# DSPCONN_0-3.net
KiCad netlist of a schematic drawn in Altium Designer
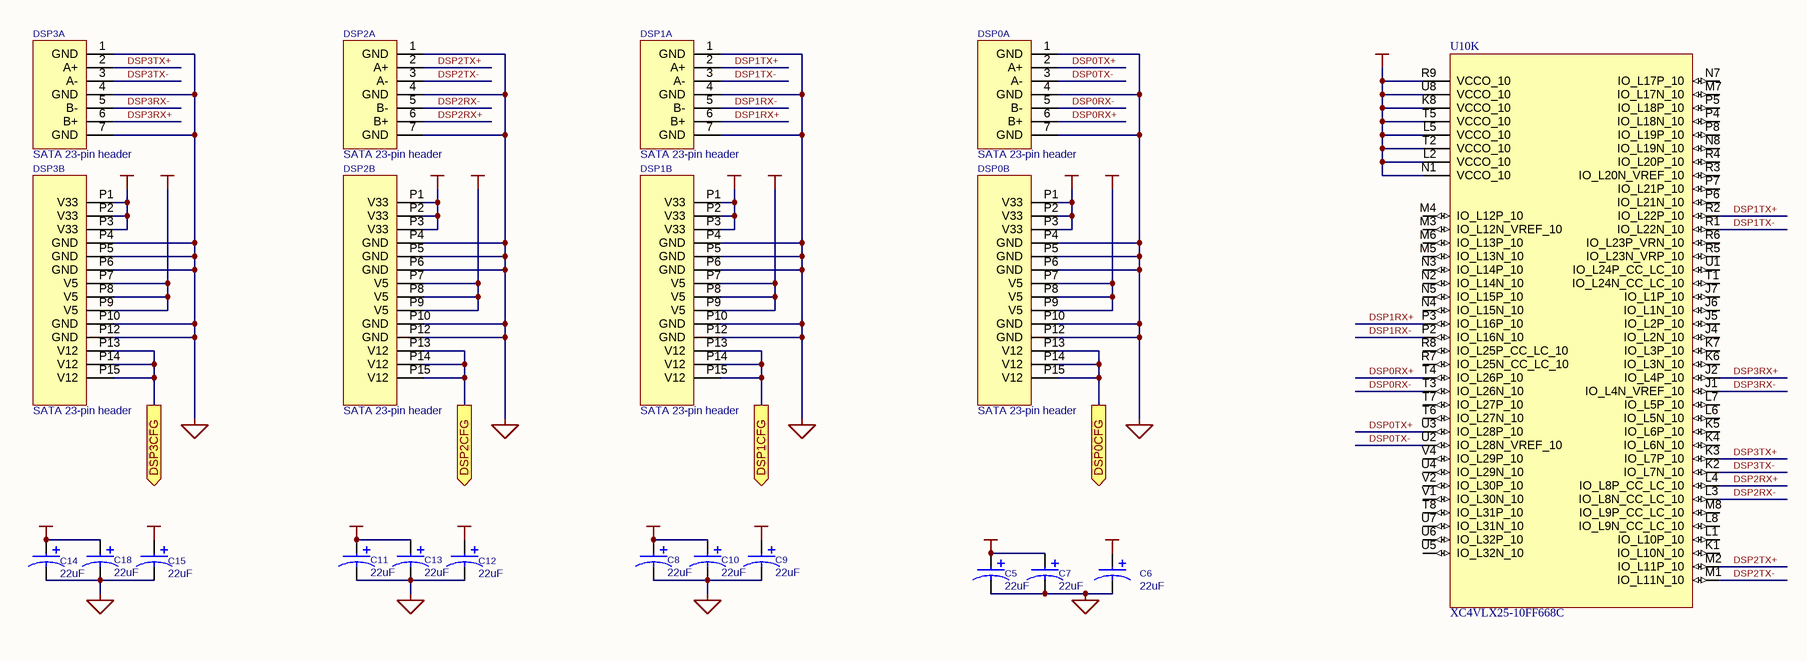
[diagram p0: DSPCONN.0-3.SCHDOC]

(export (version "E")
  (design (tool "Eeschema 10.0.6"))
  (components
    (comp (ref "C5")
      (value "22uF")
      (footprint "6032")
      (description "Standard Capacitor")
      (libsource (lib "parts") (part "POLCAP2"))
    )
    (comp (ref "C6")
      (value "22uF")
      (footprint "6032")
      (description "Standard Capacitor")
      (libsource (lib "parts") (part "POLCAP2"))
    )
    (comp (ref "C7")
      (value "22uF")
      (footprint "6032")
      (description "Standard Capacitor")
      (libsource (lib "parts") (part "POLCAP2"))
    )
    (comp (ref "C8")
      (value "22uF")
      (footprint "6032")
      (description "Standard Capacitor")
      (libsource (lib "parts") (part "POLCAP2"))
    )
    (comp (ref "C9")
      (value "22uF")
      (footprint "6032")
      (description "Standard Capacitor")
      (libsource (lib "parts") (part "POLCAP2"))
    )
    (comp (ref "C10")
      (value "22uF")
      (footprint "6032")
      (description "Standard Capacitor")
      (libsource (lib "parts") (part "POLCAP2"))
    )
    (comp (ref "C11")
      (value "22uF")
      (footprint "6032")
      (description "Standard Capacitor")
      (libsource (lib "parts") (part "POLCAP2"))
    )
    (comp (ref "C12")
      (value "22uF")
      (footprint "6032")
      (description "Standard Capacitor")
      (libsource (lib "parts") (part "POLCAP2"))
    )
    (comp (ref "C13")
      (value "22uF")
      (footprint "6032")
      (description "Standard Capacitor")
      (libsource (lib "parts") (part "POLCAP2"))
    )
    (comp (ref "C14")
      (value "22uF")
      (footprint "6032")
      (description "Standard Capacitor")
      (libsource (lib "parts") (part "POLCAP2"))
    )
    (comp (ref "C15")
      (value "22uF")
      (footprint "6032")
      (description "Standard Capacitor")
      (libsource (lib "parts") (part "POLCAP2"))
    )
    (comp (ref "C18")
      (value "22uF")
      (footprint "6032")
      (description "Standard Capacitor")
      (libsource (lib "parts") (part "POLCAP2"))
    )
    (comp (ref "DSP0")
      (value "SATA 23-pin header")
      (footprint "MOLEX 87713-1001")
      (libsource (lib "parts") (part "SATA-23"))
    )
    (comp (ref "DSP1")
      (value "SATA 23-pin header")
      (footprint "MOLEX 87713-1001")
      (libsource (lib "parts") (part "SATA-23"))
    )
    (comp (ref "DSP2")
      (value "SATA 23-pin header")
      (footprint "MOLEX 87713-1001")
      (libsource (lib "parts") (part "SATA-23"))
    )
    (comp (ref "DSP3")
      (value "SATA 23-pin header")
      (footprint "MOLEX 87713-1001")
      (libsource (lib "parts") (part "SATA-23"))
    )
    (comp (ref "U10")
      (value "XC4VLX25-10FF668C")
      (footprint "Xilinx FF668")
      (description "Xilinx Virtex-4")
      (libsource (lib "parts") (part "XC4VLX25-10FF668C"))
    )
  )
  (nets
    (net (code "1") (name "+2.5VCC") (class "Default")
      (node (ref "U10") (pin "K8") (pinfunction "VCCO_10_K8") (pintype "power_in"))
      (node (ref "U10") (pin "L2") (pinfunction "VCCO_10_L2") (pintype "power_in"))
      (node (ref "U10") (pin "L5") (pinfunction "VCCO_10_L5") (pintype "power_in"))
      (node (ref "U10") (pin "N1") (pinfunction "VCCO_10_N1") (pintype "power_in"))
      (node (ref "U10") (pin "R9") (pinfunction "VCCO_10_R9") (pintype "power_in"))
      (node (ref "U10") (pin "T2") (pinfunction "VCCO_10_T2") (pintype "power_in"))
      (node (ref "U10") (pin "T5") (pinfunction "VCCO_10_T5") (pintype "power_in"))
      (node (ref "U10") (pin "U8") (pinfunction "VCCO_10_U8") (pintype "power_in"))
    )
    (net (code "2") (name "+5VCC") (class "Default")
      (node (ref "C12") (pin "1") (pintype "passive"))
      (node (ref "C15") (pin "1") (pintype "passive"))
      (node (ref "C6") (pin "1") (pintype "passive"))
      (node (ref "C9") (pin "1") (pintype "passive"))
      (node (ref "DSP0") (pin "P7") (pinfunction "V5_P7") (pintype "passive"))
      (node (ref "DSP0") (pin "P8") (pinfunction "V5_P8") (pintype "passive"))
      (node (ref "DSP0") (pin "P9") (pinfunction "V5_P9") (pintype "passive"))
      (node (ref "DSP1") (pin "P7") (pinfunction "V5_P7") (pintype "passive"))
      (node (ref "DSP1") (pin "P8") (pinfunction "V5_P8") (pintype "passive"))
      (node (ref "DSP1") (pin "P9") (pinfunction "V5_P9") (pintype "passive"))
      (node (ref "DSP2") (pin "P7") (pinfunction "V5_P7") (pintype "passive"))
      (node (ref "DSP2") (pin "P8") (pinfunction "V5_P8") (pintype "passive"))
      (node (ref "DSP2") (pin "P9") (pinfunction "V5_P9") (pintype "passive"))
      (node (ref "DSP3") (pin "P7") (pinfunction "V5_P7") (pintype "passive"))
      (node (ref "DSP3") (pin "P8") (pinfunction "V5_P8") (pintype "passive"))
      (node (ref "DSP3") (pin "P9") (pinfunction "V5_P9") (pintype "passive"))
    )
    (net (code "3") (name "/DSP0CFG") (class "Default")
      (node (ref "DSP0") (pin "P13") (pinfunction "V12_P13") (pintype "passive"))
      (node (ref "DSP0") (pin "P14") (pinfunction "V12_P14") (pintype "passive"))
      (node (ref "DSP0") (pin "P15") (pinfunction "V12_P15") (pintype "passive"))
    )
    (net (code "4") (name "/DSP0RX+") (class "Default")
      (node (ref "DSP0") (pin "6") (pinfunction "B+_6") (pintype "passive"))
      (node (ref "U10") (pin "T4") (pinfunction "IO_L26P_10_T4") (pintype "bidirectional"))
    )
    (net (code "5") (name "/DSP0RX-") (class "Default")
      (node (ref "DSP0") (pin "5") (pinfunction "B-_5") (pintype "passive"))
      (node (ref "U10") (pin "T3") (pinfunction "IO_L26N_10_T3") (pintype "bidirectional"))
    )
    (net (code "6") (name "/DSP0TX+") (class "Default")
      (node (ref "DSP0") (pin "2") (pinfunction "A+_2") (pintype "passive"))
      (node (ref "U10") (pin "U3") (pinfunction "IO_L28P_10_U3") (pintype "bidirectional"))
    )
    (net (code "7") (name "/DSP0TX-") (class "Default")
      (node (ref "DSP0") (pin "3") (pinfunction "A-_3") (pintype "passive"))
      (node (ref "U10") (pin "U2") (pinfunction "IO_L28N_VREF_10_U2") (pintype "bidirectional"))
    )
    (net (code "8") (name "/DSP1CFG") (class "Default")
      (node (ref "DSP1") (pin "P13") (pinfunction "V12_P13") (pintype "passive"))
      (node (ref "DSP1") (pin "P14") (pinfunction "V12_P14") (pintype "passive"))
      (node (ref "DSP1") (pin "P15") (pinfunction "V12_P15") (pintype "passive"))
    )
    (net (code "9") (name "/DSP1RX+") (class "Default")
      (node (ref "DSP1") (pin "6") (pinfunction "B+_6") (pintype "passive"))
      (node (ref "U10") (pin "P3") (pinfunction "IO_L16P_10_P3") (pintype "bidirectional"))
    )
    (net (code "10") (name "/DSP1RX-") (class "Default")
      (node (ref "DSP1") (pin "5") (pinfunction "B-_5") (pintype "passive"))
      (node (ref "U10") (pin "P2") (pinfunction "IO_L16N_10_P2") (pintype "bidirectional"))
    )
    (net (code "11") (name "/DSP1TX+") (class "Default")
      (node (ref "DSP1") (pin "2") (pinfunction "A+_2") (pintype "passive"))
      (node (ref "U10") (pin "R2") (pinfunction "IO_L22P_10_R2") (pintype "bidirectional"))
    )
    (net (code "12") (name "/DSP1TX-") (class "Default")
      (node (ref "DSP1") (pin "3") (pinfunction "A-_3") (pintype "passive"))
      (node (ref "U10") (pin "R1") (pinfunction "IO_L22N_10_R1") (pintype "bidirectional"))
    )
    (net (code "13") (name "/DSP2CFG") (class "Default")
      (node (ref "DSP2") (pin "P13") (pinfunction "V12_P13") (pintype "passive"))
      (node (ref "DSP2") (pin "P14") (pinfunction "V12_P14") (pintype "passive"))
      (node (ref "DSP2") (pin "P15") (pinfunction "V12_P15") (pintype "passive"))
    )
    (net (code "14") (name "/DSP2RX+") (class "Default")
      (node (ref "DSP2") (pin "6") (pinfunction "B+_6") (pintype "passive"))
      (node (ref "U10") (pin "L4") (pinfunction "IO_L8P_CC_LC_10_L4") (pintype "bidirectional"))
    )
    (net (code "15") (name "/DSP2RX-") (class "Default")
      (node (ref "DSP2") (pin "5") (pinfunction "B-_5") (pintype "passive"))
      (node (ref "U10") (pin "L3") (pinfunction "IO_L8N_CC_LC_10_L3") (pintype "bidirectional"))
    )
    (net (code "16") (name "/DSP2TX+") (class "Default")
      (node (ref "DSP2") (pin "2") (pinfunction "A+_2") (pintype "passive"))
      (node (ref "U10") (pin "M2") (pinfunction "IO_L11P_10_M2") (pintype "bidirectional"))
    )
    (net (code "17") (name "/DSP2TX-") (class "Default")
      (node (ref "DSP2") (pin "3") (pinfunction "A-_3") (pintype "passive"))
      (node (ref "U10") (pin "M1") (pinfunction "IO_L11N_10_M1") (pintype "bidirectional"))
    )
    (net (code "18") (name "/DSP3CFG") (class "Default")
      (node (ref "DSP3") (pin "P13") (pinfunction "V12_P13") (pintype "passive"))
      (node (ref "DSP3") (pin "P14") (pinfunction "V12_P14") (pintype "passive"))
      (node (ref "DSP3") (pin "P15") (pinfunction "V12_P15") (pintype "passive"))
    )
    (net (code "19") (name "/DSP3RX+") (class "Default")
      (node (ref "DSP3") (pin "6") (pinfunction "B+_6") (pintype "passive"))
      (node (ref "U10") (pin "J2") (pinfunction "IO_L4P_10_J2") (pintype "bidirectional"))
    )
    (net (code "20") (name "/DSP3RX-") (class "Default")
      (node (ref "DSP3") (pin "5") (pinfunction "B-_5") (pintype "passive"))
      (node (ref "U10") (pin "J1") (pinfunction "IO_L4N_VREF_10_J1") (pintype "bidirectional"))
    )
    (net (code "21") (name "/DSP3TX+") (class "Default")
      (node (ref "DSP3") (pin "2") (pinfunction "A+_2") (pintype "passive"))
      (node (ref "U10") (pin "K3") (pinfunction "IO_L7P_10_K3") (pintype "bidirectional"))
    )
    (net (code "22") (name "/DSP3TX-") (class "Default")
      (node (ref "DSP3") (pin "3") (pinfunction "A-_3") (pintype "passive"))
      (node (ref "U10") (pin "K2") (pinfunction "IO_L7N_10_K2") (pintype "bidirectional"))
    )
    (net (code "23") (name "GND") (class "Default")
      (node (ref "C10") (pin "2") (pintype "passive"))
      (node (ref "C11") (pin "2") (pintype "passive"))
      (node (ref "C12") (pin "2") (pintype "passive"))
      (node (ref "C13") (pin "2") (pintype "passive"))
      (node (ref "C14") (pin "2") (pintype "passive"))
      (node (ref "C15") (pin "2") (pintype "passive"))
      (node (ref "C18") (pin "2") (pintype "passive"))
      (node (ref "C5") (pin "2") (pintype "passive"))
      (node (ref "C6") (pin "2") (pintype "passive"))
      (node (ref "C7") (pin "2") (pintype "passive"))
      (node (ref "C8") (pin "2") (pintype "passive"))
      (node (ref "C9") (pin "2") (pintype "passive"))
      (node (ref "DSP0") (pin "1") (pinfunction "GND_1") (pintype "passive"))
      (node (ref "DSP0") (pin "4") (pinfunction "GND_4") (pintype "passive"))
      (node (ref "DSP0") (pin "7") (pinfunction "GND_7") (pintype "passive"))
      (node (ref "DSP0") (pin "P10") (pinfunction "GND_P10") (pintype "passive"))
      (node (ref "DSP0") (pin "P12") (pinfunction "GND_P12") (pintype "passive"))
      (node (ref "DSP0") (pin "P4") (pinfunction "GND_P4") (pintype "passive"))
      (node (ref "DSP0") (pin "P5") (pinfunction "GND_P5") (pintype "passive"))
      (node (ref "DSP0") (pin "P6") (pinfunction "GND_P6") (pintype "passive"))
      (node (ref "DSP1") (pin "1") (pinfunction "GND_1") (pintype "passive"))
      (node (ref "DSP1") (pin "4") (pinfunction "GND_4") (pintype "passive"))
      (node (ref "DSP1") (pin "7") (pinfunction "GND_7") (pintype "passive"))
      (node (ref "DSP1") (pin "P10") (pinfunction "GND_P10") (pintype "passive"))
      (node (ref "DSP1") (pin "P12") (pinfunction "GND_P12") (pintype "passive"))
      (node (ref "DSP1") (pin "P4") (pinfunction "GND_P4") (pintype "passive"))
      (node (ref "DSP1") (pin "P5") (pinfunction "GND_P5") (pintype "passive"))
      (node (ref "DSP1") (pin "P6") (pinfunction "GND_P6") (pintype "passive"))
      (node (ref "DSP2") (pin "1") (pinfunction "GND_1") (pintype "passive"))
      (node (ref "DSP2") (pin "4") (pinfunction "GND_4") (pintype "passive"))
      (node (ref "DSP2") (pin "7") (pinfunction "GND_7") (pintype "passive"))
      (node (ref "DSP2") (pin "P10") (pinfunction "GND_P10") (pintype "passive"))
      (node (ref "DSP2") (pin "P12") (pinfunction "GND_P12") (pintype "passive"))
      (node (ref "DSP2") (pin "P4") (pinfunction "GND_P4") (pintype "passive"))
      (node (ref "DSP2") (pin "P5") (pinfunction "GND_P5") (pintype "passive"))
      (node (ref "DSP2") (pin "P6") (pinfunction "GND_P6") (pintype "passive"))
      (node (ref "DSP3") (pin "1") (pinfunction "GND_1") (pintype "passive"))
      (node (ref "DSP3") (pin "4") (pinfunction "GND_4") (pintype "passive"))
      (node (ref "DSP3") (pin "7") (pinfunction "GND_7") (pintype "passive"))
      (node (ref "DSP3") (pin "P10") (pinfunction "GND_P10") (pintype "passive"))
      (node (ref "DSP3") (pin "P12") (pinfunction "GND_P12") (pintype "passive"))
      (node (ref "DSP3") (pin "P4") (pinfunction "GND_P4") (pintype "passive"))
      (node (ref "DSP3") (pin "P5") (pinfunction "GND_P5") (pintype "passive"))
      (node (ref "DSP3") (pin "P6") (pinfunction "GND_P6") (pintype "passive"))
    )
    (net (code "24") (name "VCC") (class "Default")
      (node (ref "C10") (pin "1") (pintype "passive"))
      (node (ref "C11") (pin "1") (pintype "passive"))
      (node (ref "C13") (pin "1") (pintype "passive"))
      (node (ref "C14") (pin "1") (pintype "passive"))
      (node (ref "C18") (pin "1") (pintype "passive"))
      (node (ref "C5") (pin "1") (pintype "passive"))
      (node (ref "C7") (pin "1") (pintype "passive"))
      (node (ref "C8") (pin "1") (pintype "passive"))
      (node (ref "DSP0") (pin "P1") (pinfunction "V33_P1") (pintype "passive"))
      (node (ref "DSP0") (pin "P2") (pinfunction "V33_P2") (pintype "passive"))
      (node (ref "DSP0") (pin "P3") (pinfunction "V33_P3") (pintype "passive"))
      (node (ref "DSP1") (pin "P1") (pinfunction "V33_P1") (pintype "passive"))
      (node (ref "DSP1") (pin "P2") (pinfunction "V33_P2") (pintype "passive"))
      (node (ref "DSP1") (pin "P3") (pinfunction "V33_P3") (pintype "passive"))
      (node (ref "DSP2") (pin "P1") (pinfunction "V33_P1") (pintype "passive"))
      (node (ref "DSP2") (pin "P2") (pinfunction "V33_P2") (pintype "passive"))
      (node (ref "DSP2") (pin "P3") (pinfunction "V33_P3") (pintype "passive"))
      (node (ref "DSP3") (pin "P1") (pinfunction "V33_P1") (pintype "passive"))
      (node (ref "DSP3") (pin "P2") (pinfunction "V33_P2") (pintype "passive"))
      (node (ref "DSP3") (pin "P3") (pinfunction "V33_P3") (pintype "passive"))
    )
    (net (code "25") (name "unconnected-(U10K-IO_L1N_10-PadJ6)") (class "Default")
      (node (ref "U10") (pin "J6") (pinfunction "IO_L1N_10_J6") (pintype "bidirectional"))
    )
    (net (code "26") (name "unconnected-(U10K-IO_L1P_10-PadJ7)") (class "Default")
      (node (ref "U10") (pin "J7") (pinfunction "IO_L1P_10_J7") (pintype "bidirectional"))
    )
    (net (code "27") (name "unconnected-(U10K-IO_L2N_10-PadJ4)") (class "Default")
      (node (ref "U10") (pin "J4") (pinfunction "IO_L2N_10_J4") (pintype "bidirectional"))
    )
    (net (code "28") (name "unconnected-(U10K-IO_L2P_10-PadJ5)") (class "Default")
      (node (ref "U10") (pin "J5") (pinfunction "IO_L2P_10_J5") (pintype "bidirectional"))
    )
    (net (code "29") (name "unconnected-(U10K-IO_L3N_10-PadK6)") (class "Default")
      (node (ref "U10") (pin "K6") (pinfunction "IO_L3N_10_K6") (pintype "bidirectional"))
    )
    (net (code "30") (name "unconnected-(U10K-IO_L3P_10-PadK7)") (class "Default")
      (node (ref "U10") (pin "K7") (pinfunction "IO_L3P_10_K7") (pintype "bidirectional"))
    )
    (net (code "31") (name "unconnected-(U10K-IO_L5N_10-PadL6)") (class "Default")
      (node (ref "U10") (pin "L6") (pinfunction "IO_L5N_10_L6") (pintype "bidirectional"))
    )
    (net (code "32") (name "unconnected-(U10K-IO_L5P_10-PadL7)") (class "Default")
      (node (ref "U10") (pin "L7") (pinfunction "IO_L5P_10_L7") (pintype "bidirectional"))
    )
    (net (code "33") (name "unconnected-(U10K-IO_L6N_10-PadK4)") (class "Default")
      (node (ref "U10") (pin "K4") (pinfunction "IO_L6N_10_K4") (pintype "bidirectional"))
    )
    (net (code "34") (name "unconnected-(U10K-IO_L6P_10-PadK5)") (class "Default")
      (node (ref "U10") (pin "K5") (pinfunction "IO_L6P_10_K5") (pintype "bidirectional"))
    )
    (net (code "35") (name "unconnected-(U10K-IO_L9N_CC_LC_10-PadL8)") (class "Default")
      (node (ref "U10") (pin "L8") (pinfunction "IO_L9N_CC_LC_10_L8") (pintype "bidirectional"))
    )
    (net (code "36") (name "unconnected-(U10K-IO_L9P_CC_LC_10-PadM8)") (class "Default")
      (node (ref "U10") (pin "M8") (pinfunction "IO_L9P_CC_LC_10_M8") (pintype "bidirectional"))
    )
    (net (code "37") (name "unconnected-(U10K-IO_L10N_10-PadK1)") (class "Default")
      (node (ref "U10") (pin "K1") (pinfunction "IO_L10N_10_K1") (pintype "bidirectional"))
    )
    (net (code "38") (name "unconnected-(U10K-IO_L10P_10-PadL1)") (class "Default")
      (node (ref "U10") (pin "L1") (pinfunction "IO_L10P_10_L1") (pintype "bidirectional"))
    )
    (net (code "39") (name "unconnected-(U10K-IO_L12N_VREF_10-PadM3)") (class "Default")
      (node (ref "U10") (pin "M3") (pinfunction "IO_L12N_VREF_10_M3") (pintype "bidirectional"))
    )
    (net (code "40") (name "unconnected-(U10K-IO_L12P_10-PadM4)") (class "Default")
      (node (ref "U10") (pin "M4") (pinfunction "IO_L12P_10_M4") (pintype "bidirectional"))
    )
    (net (code "41") (name "unconnected-(U10K-IO_L13N_10-PadM5)") (class "Default")
      (node (ref "U10") (pin "M5") (pinfunction "IO_L13N_10_M5") (pintype "bidirectional"))
    )
    (net (code "42") (name "unconnected-(U10K-IO_L13P_10-PadM6)") (class "Default")
      (node (ref "U10") (pin "M6") (pinfunction "IO_L13P_10_M6") (pintype "bidirectional"))
    )
    (net (code "43") (name "unconnected-(U10K-IO_L14N_10-PadN2)") (class "Default")
      (node (ref "U10") (pin "N2") (pinfunction "IO_L14N_10_N2") (pintype "bidirectional"))
    )
    (net (code "44") (name "unconnected-(U10K-IO_L14P_10-PadN3)") (class "Default")
      (node (ref "U10") (pin "N3") (pinfunction "IO_L14P_10_N3") (pintype "bidirectional"))
    )
    (net (code "45") (name "unconnected-(U10K-IO_L15N_10-PadN4)") (class "Default")
      (node (ref "U10") (pin "N4") (pinfunction "IO_L15N_10_N4") (pintype "bidirectional"))
    )
    (net (code "46") (name "unconnected-(U10K-IO_L15P_10-PadN5)") (class "Default")
      (node (ref "U10") (pin "N5") (pinfunction "IO_L15P_10_N5") (pintype "bidirectional"))
    )
    (net (code "47") (name "unconnected-(U10K-IO_L17N_10-PadM7)") (class "Default")
      (node (ref "U10") (pin "M7") (pinfunction "IO_L17N_10_M7") (pintype "bidirectional"))
    )
    (net (code "48") (name "unconnected-(U10K-IO_L17P_10-PadN7)") (class "Default")
      (node (ref "U10") (pin "N7") (pinfunction "IO_L17P_10_N7") (pintype "bidirectional"))
    )
    (net (code "49") (name "unconnected-(U10K-IO_L18N_10-PadP4)") (class "Default")
      (node (ref "U10") (pin "P4") (pinfunction "IO_L18N_10_P4") (pintype "bidirectional"))
    )
    (net (code "50") (name "unconnected-(U10K-IO_L18P_10-PadP5)") (class "Default")
      (node (ref "U10") (pin "P5") (pinfunction "IO_L18P_10_P5") (pintype "bidirectional"))
    )
    (net (code "51") (name "unconnected-(U10K-IO_L19N_10-PadN8)") (class "Default")
      (node (ref "U10") (pin "N8") (pinfunction "IO_L19N_10_N8") (pintype "bidirectional"))
    )
    (net (code "52") (name "unconnected-(U10K-IO_L19P_10-PadP8)") (class "Default")
      (node (ref "U10") (pin "P8") (pinfunction "IO_L19P_10_P8") (pintype "bidirectional"))
    )
    (net (code "53") (name "unconnected-(U10K-IO_L20N_VREF_10-PadR3)") (class "Default")
      (node (ref "U10") (pin "R3") (pinfunction "IO_L20N_VREF_10_R3") (pintype "bidirectional"))
    )
    (net (code "54") (name "unconnected-(U10K-IO_L20P_10-PadR4)") (class "Default")
      (node (ref "U10") (pin "R4") (pinfunction "IO_L20P_10_R4") (pintype "bidirectional"))
    )
    (net (code "55") (name "unconnected-(U10K-IO_L21N_10-PadP6)") (class "Default")
      (node (ref "U10") (pin "P6") (pinfunction "IO_L21N_10_P6") (pintype "bidirectional"))
    )
    (net (code "56") (name "unconnected-(U10K-IO_L21P_10-PadP7)") (class "Default")
      (node (ref "U10") (pin "P7") (pinfunction "IO_L21P_10_P7") (pintype "bidirectional"))
    )
    (net (code "57") (name "unconnected-(U10K-IO_L23N_VRP_10-PadR5)") (class "Default")
      (node (ref "U10") (pin "R5") (pinfunction "IO_L23N_VRP_10_R5") (pintype "bidirectional"))
    )
    (net (code "58") (name "unconnected-(U10K-IO_L23P_VRN_10-PadR6)") (class "Default")
      (node (ref "U10") (pin "R6") (pinfunction "IO_L23P_VRN_10_R6") (pintype "bidirectional"))
    )
    (net (code "59") (name "unconnected-(U10K-IO_L24N_CC_LC_10-PadT1)") (class "Default")
      (node (ref "U10") (pin "T1") (pinfunction "IO_L24N_CC_LC_10_T1") (pintype "bidirectional"))
    )
    (net (code "60") (name "unconnected-(U10K-IO_L24P_CC_LC_10-PadU1)") (class "Default")
      (node (ref "U10") (pin "U1") (pinfunction "IO_L24P_CC_LC_10_U1") (pintype "bidirectional"))
    )
    (net (code "61") (name "unconnected-(U10K-IO_L25N_CC_LC_10-PadR7)") (class "Default")
      (node (ref "U10") (pin "R7") (pinfunction "IO_L25N_CC_LC_10_R7") (pintype "bidirectional"))
    )
    (net (code "62") (name "unconnected-(U10K-IO_L25P_CC_LC_10-PadR8)") (class "Default")
      (node (ref "U10") (pin "R8") (pinfunction "IO_L25P_CC_LC_10_R8") (pintype "bidirectional"))
    )
    (net (code "63") (name "unconnected-(U10K-IO_L27N_10-PadT6)") (class "Default")
      (node (ref "U10") (pin "T6") (pinfunction "IO_L27N_10_T6") (pintype "bidirectional"))
    )
    (net (code "64") (name "unconnected-(U10K-IO_L27P_10-PadT7)") (class "Default")
      (node (ref "U10") (pin "T7") (pinfunction "IO_L27P_10_T7") (pintype "bidirectional"))
    )
    (net (code "65") (name "unconnected-(U10K-IO_L29N_10-PadU4)") (class "Default")
      (node (ref "U10") (pin "U4") (pinfunction "IO_L29N_10_U4") (pintype "bidirectional"))
    )
    (net (code "66") (name "unconnected-(U10K-IO_L29P_10-PadV4)") (class "Default")
      (node (ref "U10") (pin "V4") (pinfunction "IO_L29P_10_V4") (pintype "bidirectional"))
    )
    (net (code "67") (name "unconnected-(U10K-IO_L30N_10-PadV1)") (class "Default")
      (node (ref "U10") (pin "V1") (pinfunction "IO_L30N_10_V1") (pintype "bidirectional"))
    )
    (net (code "68") (name "unconnected-(U10K-IO_L30P_10-PadV2)") (class "Default")
      (node (ref "U10") (pin "V2") (pinfunction "IO_L30P_10_V2") (pintype "bidirectional"))
    )
    (net (code "69") (name "unconnected-(U10K-IO_L31N_10-PadU7)") (class "Default")
      (node (ref "U10") (pin "U7") (pinfunction "IO_L31N_10_U7") (pintype "bidirectional"))
    )
    (net (code "70") (name "unconnected-(U10K-IO_L31P_10-PadT8)") (class "Default")
      (node (ref "U10") (pin "T8") (pinfunction "IO_L31P_10_T8") (pintype "bidirectional"))
    )
    (net (code "71") (name "unconnected-(U10K-IO_L32N_10-PadU5)") (class "Default")
      (node (ref "U10") (pin "U5") (pinfunction "IO_L32N_10_U5") (pintype "bidirectional"))
    )
    (net (code "72") (name "unconnected-(U10K-IO_L32P_10-PadU6)") (class "Default")
      (node (ref "U10") (pin "U6") (pinfunction "IO_L32P_10_U6") (pintype "bidirectional"))
    )
  )
)
